# eater_eeprom.net
KiCad netlist of a schematic drawn in EAGLE
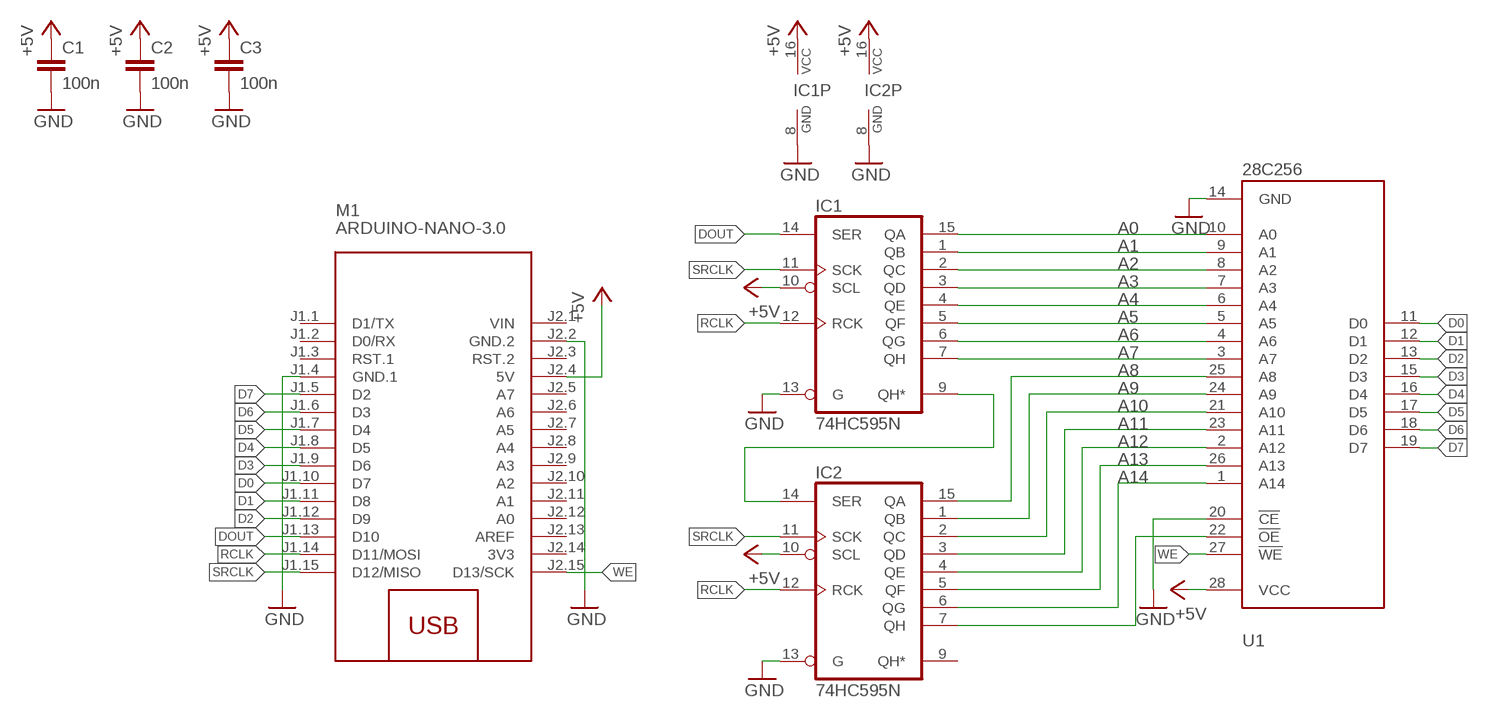
[diagram p0: schematic, sheet 1]

(export (version "E")
  (design (tool "Eeschema 10.0.6"))
  (components
    (comp (ref "C1")
      (value "100n")
      (footprint "eagle-import:C0805")
      (libsource (lib "eagle-import") (part "C-EUC0805"))
    )
    (comp (ref "C2")
      (value "100n")
      (footprint "eagle-import:C0805")
      (libsource (lib "eagle-import") (part "C-EUC0805"))
    )
    (comp (ref "C3")
      (value "100n")
      (footprint "eagle-import:C0805")
      (libsource (lib "eagle-import") (part "C-EUC0805"))
    )
    (comp (ref "IC1")
      (value "74HC595N")
      (footprint "eagle-import:DIL16")
      (libsource (lib "eagle-import") (part "74595NHC"))
    )
    (comp (ref "IC2")
      (value "74HC595N")
      (footprint "eagle-import:DIL16")
      (libsource (lib "eagle-import") (part "74595NHC"))
    )
    (comp (ref "M1")
      (value "ARDUINO-NANO-3.0")
      (footprint "eagle-import:ARDUINO-NANO-3.0")
      (libsource (lib "eagle-import") (part "ARDUINO-NANO-3.0"))
    )
    (comp (ref "U1")
      (value "28C256")
      (footprint "eagle-import:DIL28-6")
      (libsource (lib "eagle-import") (part "28C256"))
    )
  )
  (nets
    (net (code "1") (name "+5V") (class "Default")
      (node (ref "C1") (pin "1") (pinfunction "1_1") (pintype "passive"))
      (node (ref "C2") (pin "1") (pinfunction "1_1") (pintype "passive"))
      (node (ref "C3") (pin "1") (pinfunction "1_1") (pintype "passive"))
      (node (ref "IC1") (pin "10") (pinfunction "SCL_10") (pintype "input"))
      (node (ref "IC1") (pin "16") (pinfunction "VCC_16") (pintype "power_in"))
      (node (ref "IC2") (pin "10") (pinfunction "SCL_10") (pintype "input"))
      (node (ref "IC2") (pin "16") (pinfunction "VCC_16") (pintype "power_in"))
      (node (ref "M1") (pin "J2.4") (pinfunction "5V_J2.4") (pintype "power_in"))
      (node (ref "U1") (pin "28") (pinfunction "VCC_28") (pintype "power_in"))
    )
    (net (code "2") (name "/3V3") (class "Default")
      (node (ref "M1") (pin "J2.14") (pinfunction "3V3_J2.14") (pintype "power_in"))
    )
    (net (code "3") (name "/A0") (class "Default")
      (node (ref "IC1") (pin "15") (pinfunction "QA_15") (pintype "tri_state"))
      (node (ref "U1") (pin "10") (pinfunction "A0_10") (pintype "input"))
    )
    (net (code "4") (name "/A1") (class "Default")
      (node (ref "IC1") (pin "1") (pinfunction "QB_1") (pintype "tri_state"))
      (node (ref "U1") (pin "9") (pinfunction "A1_9") (pintype "input"))
    )
    (net (code "5") (name "/A2") (class "Default")
      (node (ref "IC1") (pin "2") (pinfunction "QC_2") (pintype "tri_state"))
      (node (ref "U1") (pin "8") (pinfunction "A2_8") (pintype "input"))
    )
    (net (code "6") (name "/A3") (class "Default")
      (node (ref "IC1") (pin "3") (pinfunction "QD_3") (pintype "tri_state"))
      (node (ref "U1") (pin "7") (pinfunction "A3_7") (pintype "input"))
    )
    (net (code "7") (name "/A4") (class "Default")
      (node (ref "IC1") (pin "4") (pinfunction "QE_4") (pintype "tri_state"))
      (node (ref "U1") (pin "6") (pinfunction "A4_6") (pintype "input"))
    )
    (net (code "8") (name "/A5") (class "Default")
      (node (ref "IC1") (pin "5") (pinfunction "QF_5") (pintype "tri_state"))
      (node (ref "U1") (pin "5") (pinfunction "A5_5") (pintype "input"))
    )
    (net (code "9") (name "/A6") (class "Default")
      (node (ref "IC1") (pin "6") (pinfunction "QG_6") (pintype "tri_state"))
      (node (ref "U1") (pin "4") (pinfunction "A6_4") (pintype "input"))
    )
    (net (code "10") (name "/A7") (class "Default")
      (node (ref "IC1") (pin "7") (pinfunction "QH_7") (pintype "tri_state"))
      (node (ref "U1") (pin "3") (pinfunction "A7_3") (pintype "input"))
    )
    (net (code "11") (name "/A8") (class "Default")
      (node (ref "IC2") (pin "15") (pinfunction "QA_15") (pintype "tri_state"))
      (node (ref "U1") (pin "25") (pinfunction "A8_25") (pintype "input"))
    )
    (net (code "12") (name "/A9") (class "Default")
      (node (ref "IC2") (pin "1") (pinfunction "QB_1") (pintype "tri_state"))
      (node (ref "U1") (pin "24") (pinfunction "A9_24") (pintype "input"))
    )
    (net (code "13") (name "/A10") (class "Default")
      (node (ref "IC2") (pin "2") (pinfunction "QC_2") (pintype "tri_state"))
      (node (ref "U1") (pin "21") (pinfunction "A10_21") (pintype "input"))
    )
    (net (code "14") (name "/A11") (class "Default")
      (node (ref "IC2") (pin "3") (pinfunction "QD_3") (pintype "tri_state"))
      (node (ref "U1") (pin "23") (pinfunction "A11_23") (pintype "input"))
    )
    (net (code "15") (name "/A12") (class "Default")
      (node (ref "IC2") (pin "4") (pinfunction "QE_4") (pintype "tri_state"))
      (node (ref "U1") (pin "2") (pinfunction "A12_2") (pintype "input"))
    )
    (net (code "16") (name "/A13") (class "Default")
      (node (ref "IC2") (pin "5") (pinfunction "QF_5") (pintype "tri_state"))
      (node (ref "U1") (pin "26") (pinfunction "A13_26") (pintype "input"))
    )
    (net (code "17") (name "/A14") (class "Default")
      (node (ref "IC2") (pin "6") (pinfunction "QG_6") (pintype "tri_state"))
      (node (ref "U1") (pin "1") (pinfunction "A14_1") (pintype "input"))
    )
    (net (code "18") (name "/VIN") (class "Default")
      (node (ref "M1") (pin "J2.1") (pinfunction "VIN_J2.1") (pintype "power_in"))
    )
    (net (code "19") (name "D0") (class "Default")
      (node (ref "M1") (pin "J1.10") (pinfunction "D7_J1.10") (pintype "bidirectional"))
      (node (ref "U1") (pin "11") (pinfunction "D0_11") (pintype "tri_state"))
    )
    (net (code "20") (name "D1") (class "Default")
      (node (ref "M1") (pin "J1.11") (pinfunction "D8_J1.11") (pintype "bidirectional"))
      (node (ref "U1") (pin "12") (pinfunction "D1_12") (pintype "tri_state"))
    )
    (net (code "21") (name "D2") (class "Default")
      (node (ref "M1") (pin "J1.12") (pinfunction "D9_J1.12") (pintype "bidirectional"))
      (node (ref "U1") (pin "13") (pinfunction "D2_13") (pintype "tri_state"))
    )
    (net (code "22") (name "D3") (class "Default")
      (node (ref "M1") (pin "J1.9") (pinfunction "D6_J1.9") (pintype "bidirectional"))
      (node (ref "U1") (pin "15") (pinfunction "D3_15") (pintype "tri_state"))
    )
    (net (code "23") (name "D4") (class "Default")
      (node (ref "M1") (pin "J1.8") (pinfunction "D5_J1.8") (pintype "bidirectional"))
      (node (ref "U1") (pin "16") (pinfunction "D4_16") (pintype "tri_state"))
    )
    (net (code "24") (name "D5") (class "Default")
      (node (ref "M1") (pin "J1.7") (pinfunction "D4_J1.7") (pintype "bidirectional"))
      (node (ref "U1") (pin "17") (pinfunction "D5_17") (pintype "tri_state"))
    )
    (net (code "25") (name "D6") (class "Default")
      (node (ref "M1") (pin "J1.6") (pinfunction "D3_J1.6") (pintype "bidirectional"))
      (node (ref "U1") (pin "18") (pinfunction "D6_18") (pintype "tri_state"))
    )
    (net (code "26") (name "D7") (class "Default")
      (node (ref "M1") (pin "J1.5") (pinfunction "D2_J1.5") (pintype "bidirectional"))
      (node (ref "U1") (pin "19") (pinfunction "D7_19") (pintype "tri_state"))
    )
    (net (code "27") (name "DOUT") (class "Default")
      (node (ref "IC1") (pin "14") (pinfunction "SER_14") (pintype "input"))
      (node (ref "M1") (pin "J1.13") (pinfunction "D10_J1.13") (pintype "bidirectional"))
    )
    (net (code "28") (name "GND") (class "Default")
      (node (ref "C1") (pin "2") (pinfunction "2_2") (pintype "passive"))
      (node (ref "C2") (pin "2") (pinfunction "2_2") (pintype "passive"))
      (node (ref "C3") (pin "2") (pinfunction "2_2") (pintype "passive"))
      (node (ref "IC1") (pin "13") (pinfunction "G_13") (pintype "input"))
      (node (ref "IC1") (pin "8") (pinfunction "GND_8") (pintype "power_in"))
      (node (ref "IC2") (pin "13") (pinfunction "G_13") (pintype "input"))
      (node (ref "IC2") (pin "8") (pinfunction "GND_8") (pintype "power_in"))
      (node (ref "M1") (pin "J1.4") (pinfunction "GND.1_J1.4") (pintype "power_in"))
      (node (ref "M1") (pin "J2.2") (pinfunction "GND.2_J2.2") (pintype "power_in"))
      (node (ref "U1") (pin "14") (pinfunction "GND_14") (pintype "power_in"))
      (node (ref "U1") (pin "20") (pinfunction "~{CE}_20") (pintype "input"))
    )
    (net (code "29") (name "Net-(IC1A-QH*)") (class "Default")
      (node (ref "IC1") (pin "9") (pinfunction "QH*_9") (pintype "tri_state"))
      (node (ref "IC2") (pin "14") (pinfunction "SER_14") (pintype "input"))
    )
    (net (code "30") (name "Net-(IC2A-QH)") (class "Default")
      (node (ref "IC2") (pin "7") (pinfunction "QH_7") (pintype "tri_state"))
      (node (ref "U1") (pin "22") (pinfunction "~{OE}_22") (pintype "input"))
    )
    (net (code "31") (name "RCLK") (class "Default")
      (node (ref "IC1") (pin "12") (pinfunction "RCK_12") (pintype "input"))
      (node (ref "IC2") (pin "12") (pinfunction "RCK_12") (pintype "input"))
      (node (ref "M1") (pin "J1.14") (pinfunction "D11/MOSI_J1.14") (pintype "bidirectional"))
    )
    (net (code "32") (name "SRCLK") (class "Default")
      (node (ref "IC1") (pin "11") (pinfunction "SCK_11") (pintype "input"))
      (node (ref "IC2") (pin "11") (pinfunction "SCK_11") (pintype "input"))
      (node (ref "M1") (pin "J1.15") (pinfunction "D12/MISO_J1.15") (pintype "bidirectional"))
    )
    (net (code "33") (name "WE") (class "Default")
      (node (ref "M1") (pin "J2.15") (pinfunction "D13/SCK_J2.15") (pintype "bidirectional"))
      (node (ref "U1") (pin "27") (pinfunction "~{WE}_27") (pintype "input"))
    )
    (net (code "34") (name "unconnected-(IC2A-QH*-Pad9)") (class "Default")
      (node (ref "IC2") (pin "9") (pinfunction "QH*_9") (pintype "tri_state"))
    )
    (net (code "35") (name "unconnected-(M1-A0-PadJ2.12)") (class "Default")
      (node (ref "M1") (pin "J2.12") (pinfunction "A0_J2.12") (pintype "bidirectional"))
    )
    (net (code "36") (name "unconnected-(M1-A1-PadJ2.11)") (class "Default")
      (node (ref "M1") (pin "J2.11") (pinfunction "A1_J2.11") (pintype "bidirectional"))
    )
    (net (code "37") (name "unconnected-(M1-A2-PadJ2.10)") (class "Default")
      (node (ref "M1") (pin "J2.10") (pinfunction "A2_J2.10") (pintype "bidirectional"))
    )
    (net (code "38") (name "unconnected-(M1-A3-PadJ2.9)") (class "Default")
      (node (ref "M1") (pin "J2.9") (pinfunction "A3_J2.9") (pintype "bidirectional"))
    )
    (net (code "39") (name "unconnected-(M1-A4-PadJ2.8)") (class "Default")
      (node (ref "M1") (pin "J2.8") (pinfunction "A4_J2.8") (pintype "bidirectional"))
    )
    (net (code "40") (name "unconnected-(M1-A5-PadJ2.7)") (class "Default")
      (node (ref "M1") (pin "J2.7") (pinfunction "A5_J2.7") (pintype "bidirectional"))
    )
    (net (code "41") (name "unconnected-(M1-A6-PadJ2.6)") (class "Default")
      (node (ref "M1") (pin "J2.6") (pinfunction "A6_J2.6") (pintype "bidirectional"))
    )
    (net (code "42") (name "unconnected-(M1-A7-PadJ2.5)") (class "Default")
      (node (ref "M1") (pin "J2.5") (pinfunction "A7_J2.5") (pintype "bidirectional"))
    )
    (net (code "43") (name "unconnected-(M1-AREF-PadJ2.13)") (class "Default")
      (node (ref "M1") (pin "J2.13") (pinfunction "AREF_J2.13") (pintype "bidirectional"))
    )
    (net (code "44") (name "unconnected-(M1-D0{slash}RX-PadJ1.2)") (class "Default")
      (node (ref "M1") (pin "J1.2") (pinfunction "D0/RX_J1.2") (pintype "bidirectional"))
    )
    (net (code "45") (name "unconnected-(M1-D1{slash}TX-PadJ1.1)") (class "Default")
      (node (ref "M1") (pin "J1.1") (pinfunction "D1/TX_J1.1") (pintype "bidirectional"))
    )
    (net (code "46") (name "unconnected-(M1-RST.1-PadJ1.3)") (class "Default")
      (node (ref "M1") (pin "J1.3") (pinfunction "RST.1_J1.3") (pintype "bidirectional"))
    )
    (net (code "47") (name "unconnected-(M1-RST.2-PadJ2.3)") (class "Default")
      (node (ref "M1") (pin "J2.3") (pinfunction "RST.2_J2.3") (pintype "bidirectional"))
    )
  )
)
